# MCU.net
KiCad netlist of a schematic drawn in Altium Designer
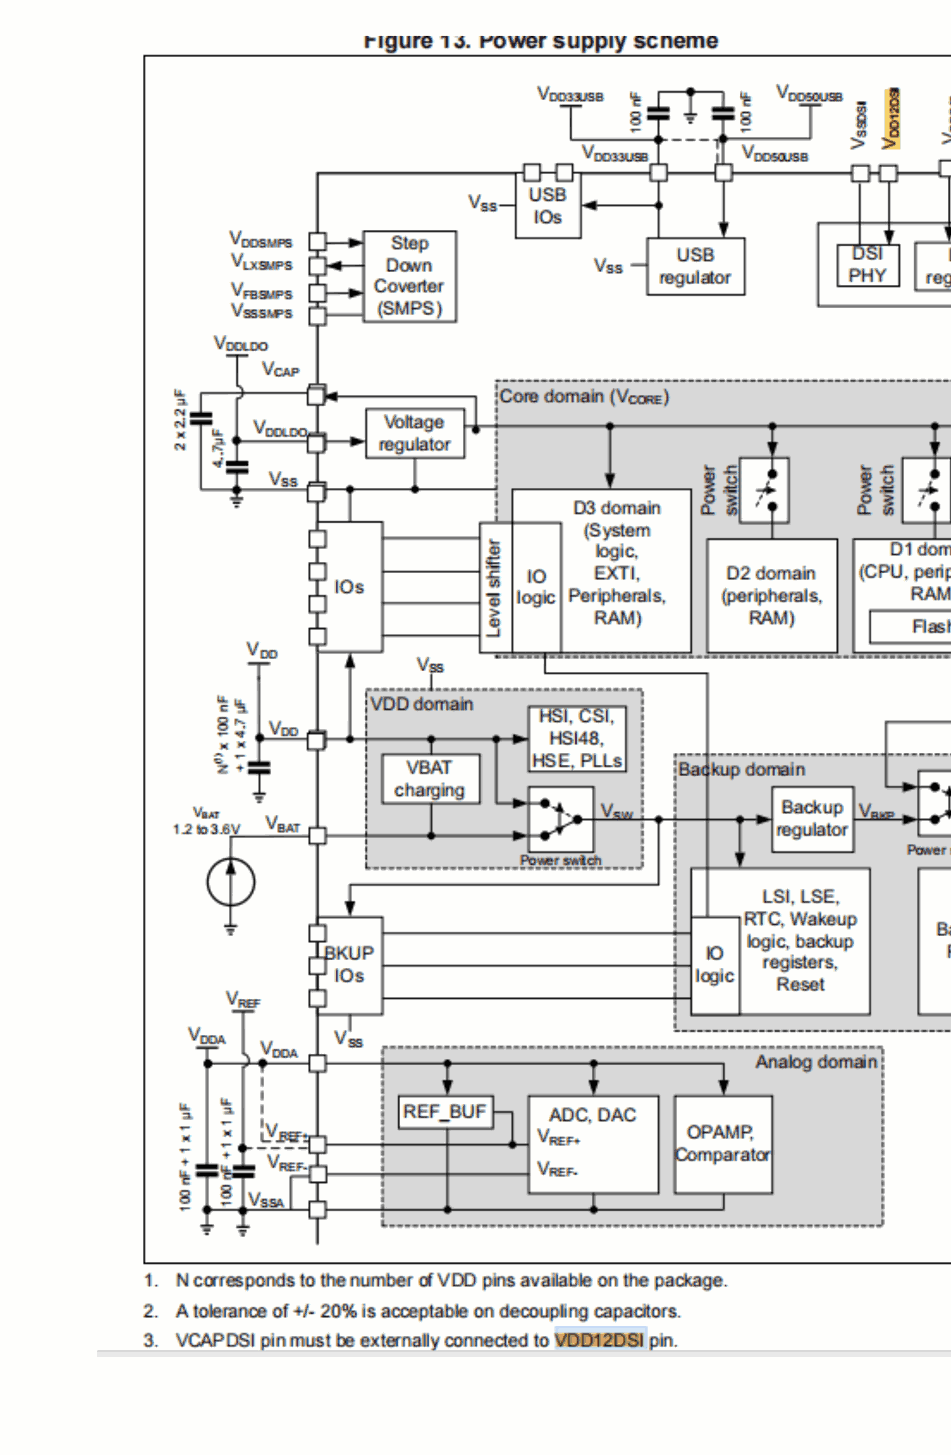
[diagram p0: MCU.SchDoc, top left]
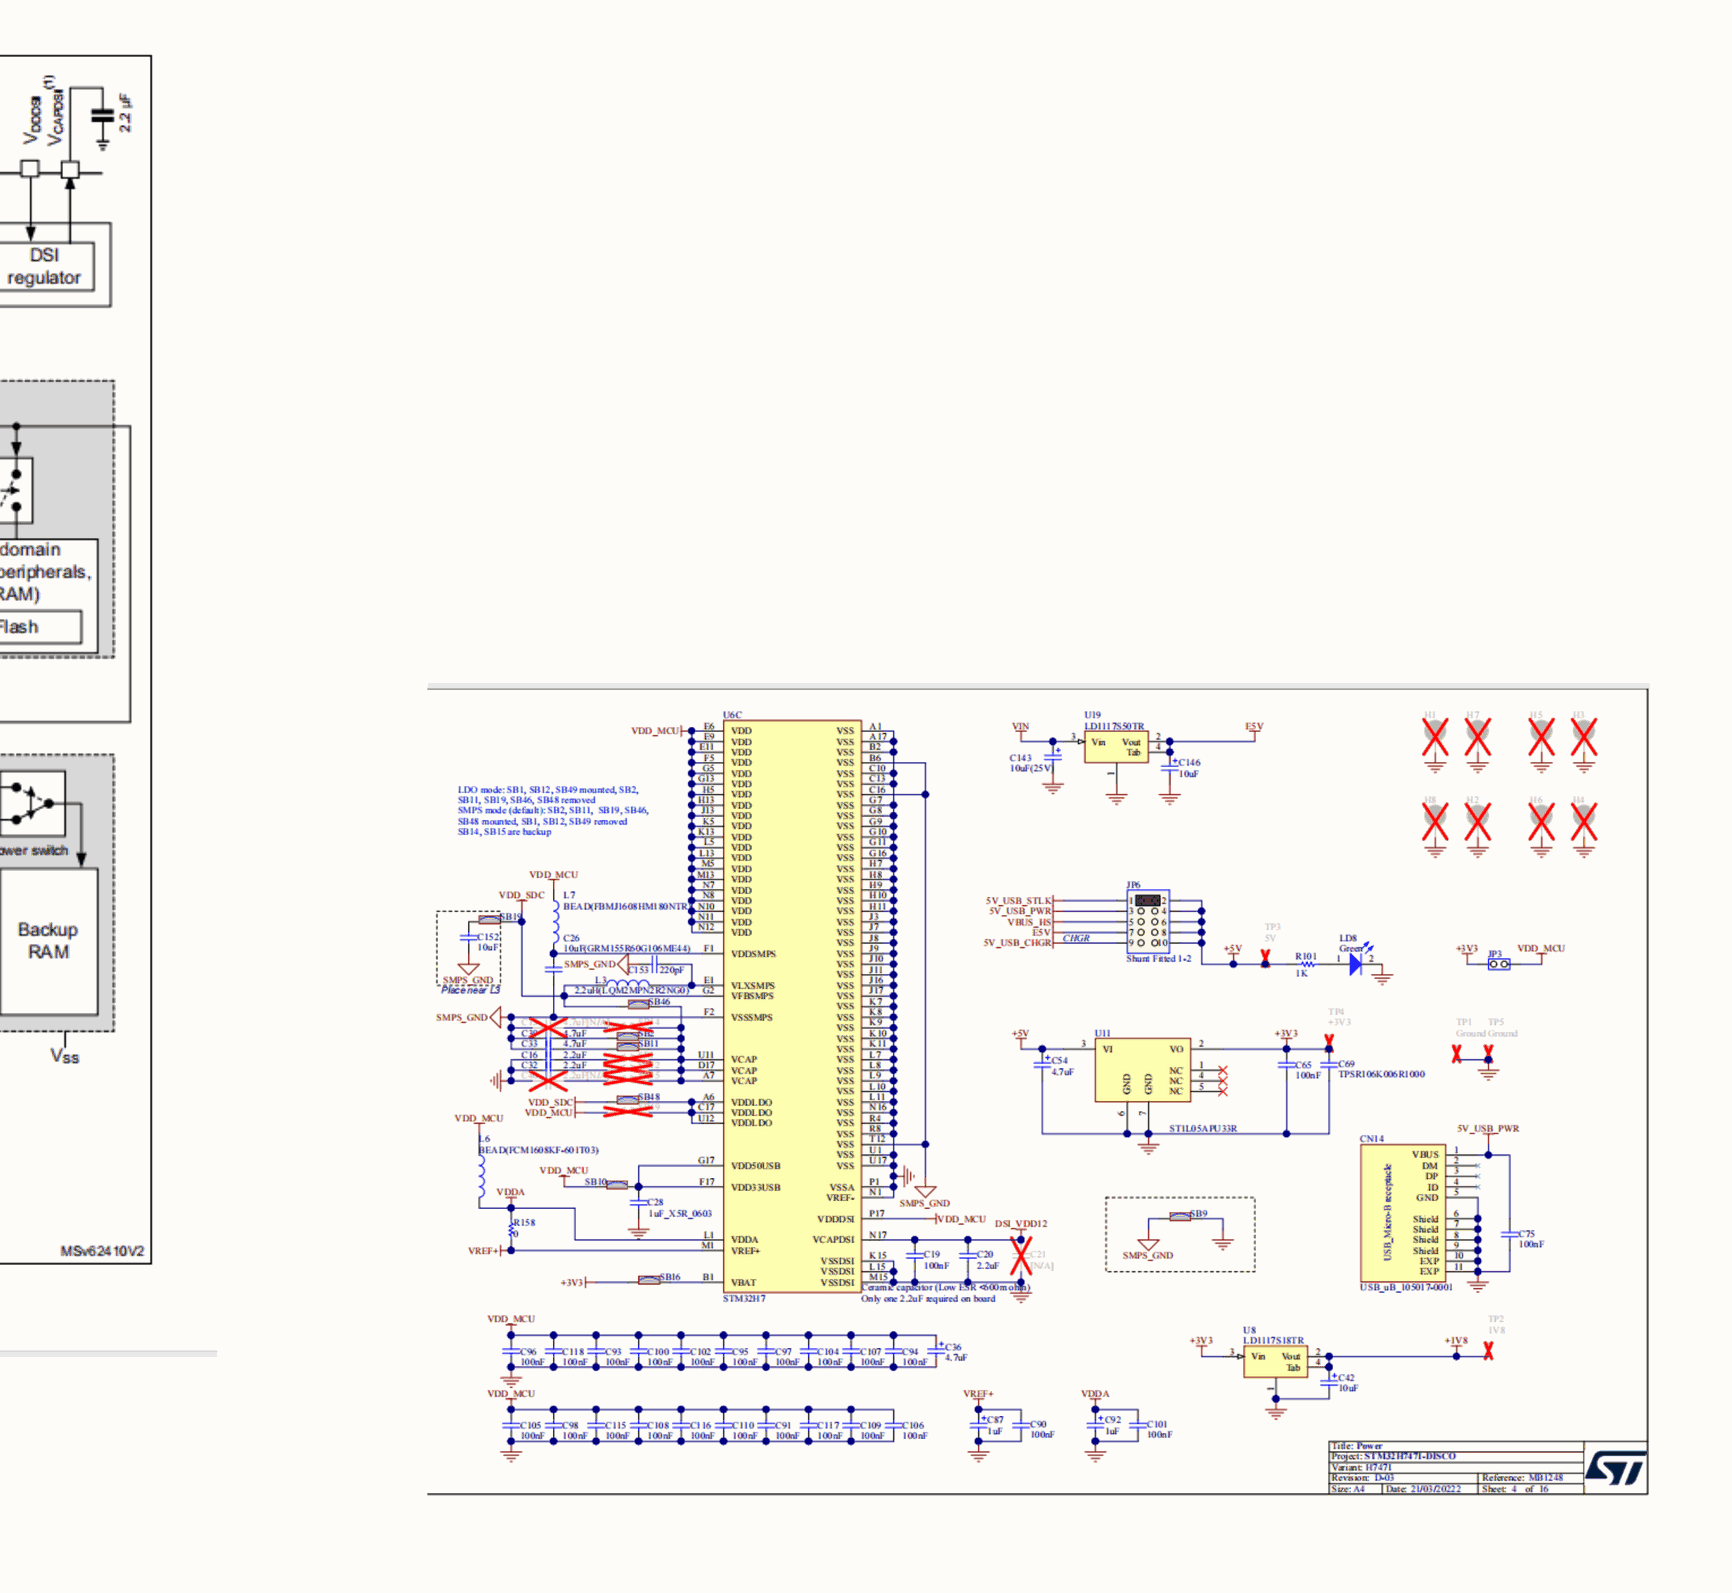
[diagram p1: MCU.SchDoc, top middle]
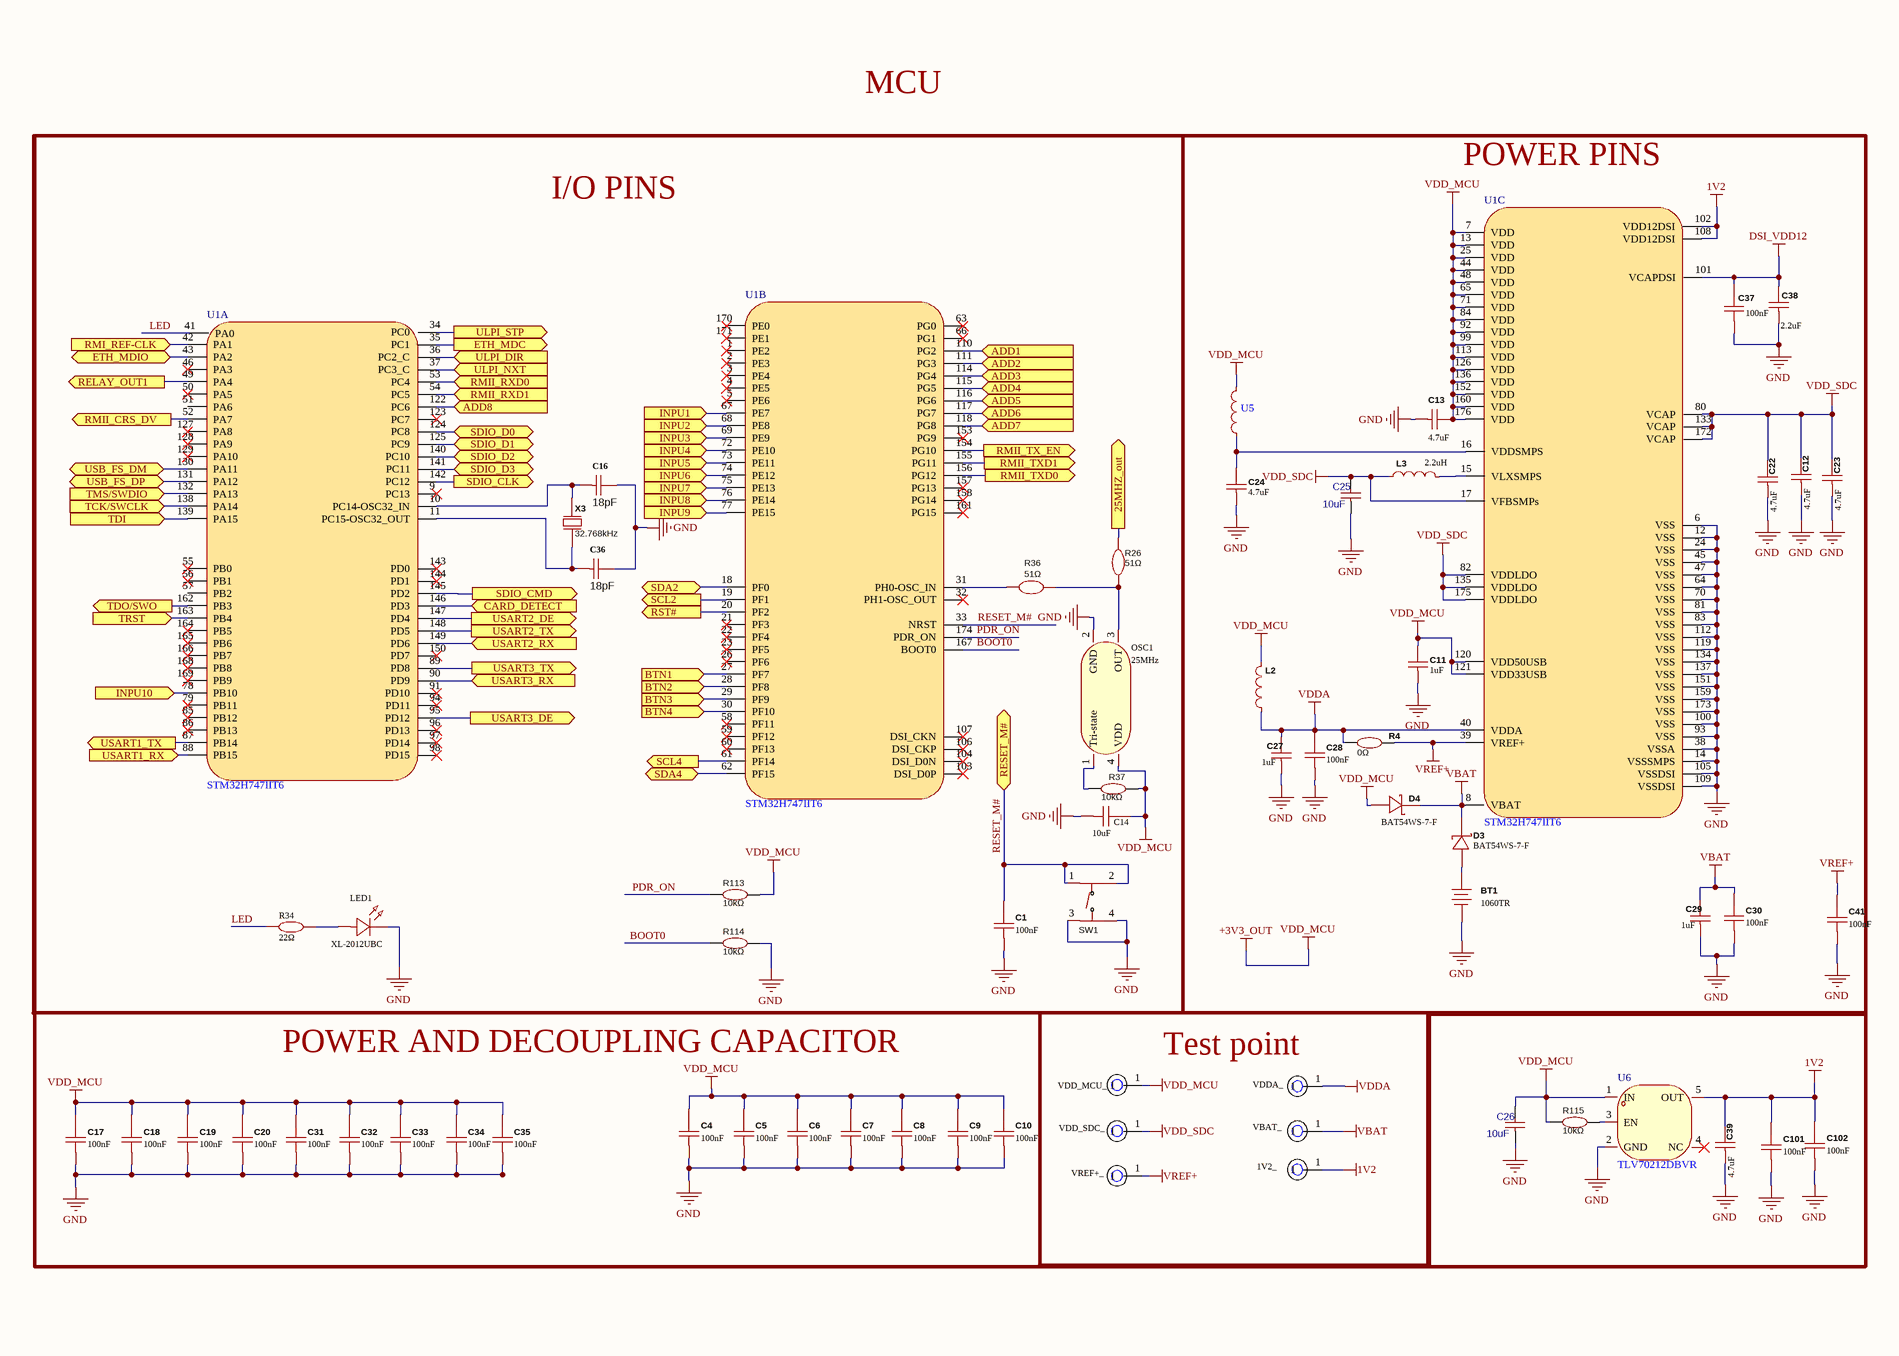
[diagram p2: MCU.SchDoc, bottom left]
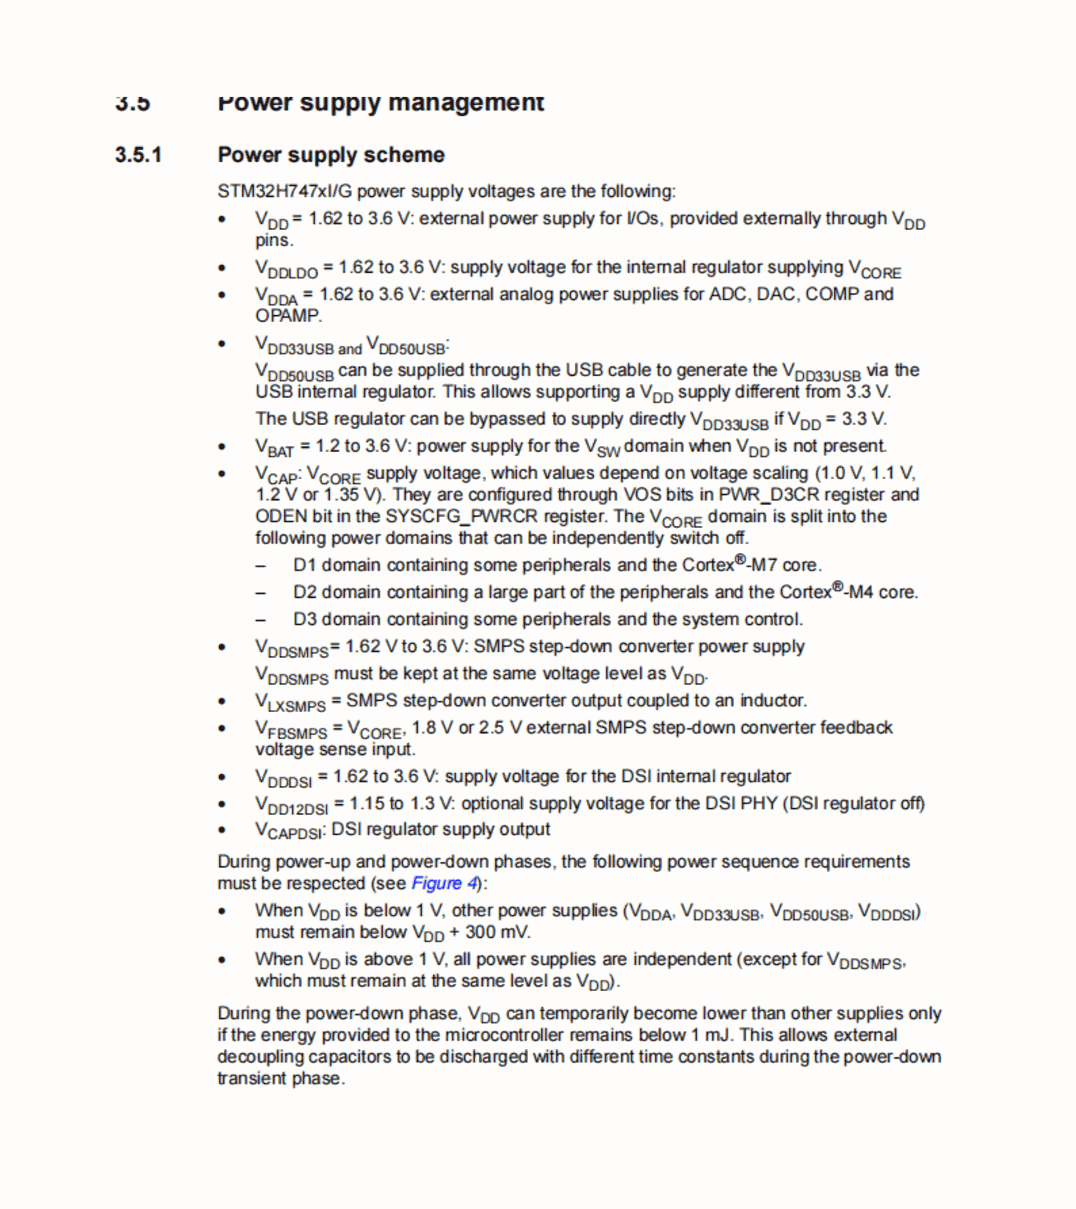
[diagram p3: MCU.SchDoc, bottom middle]
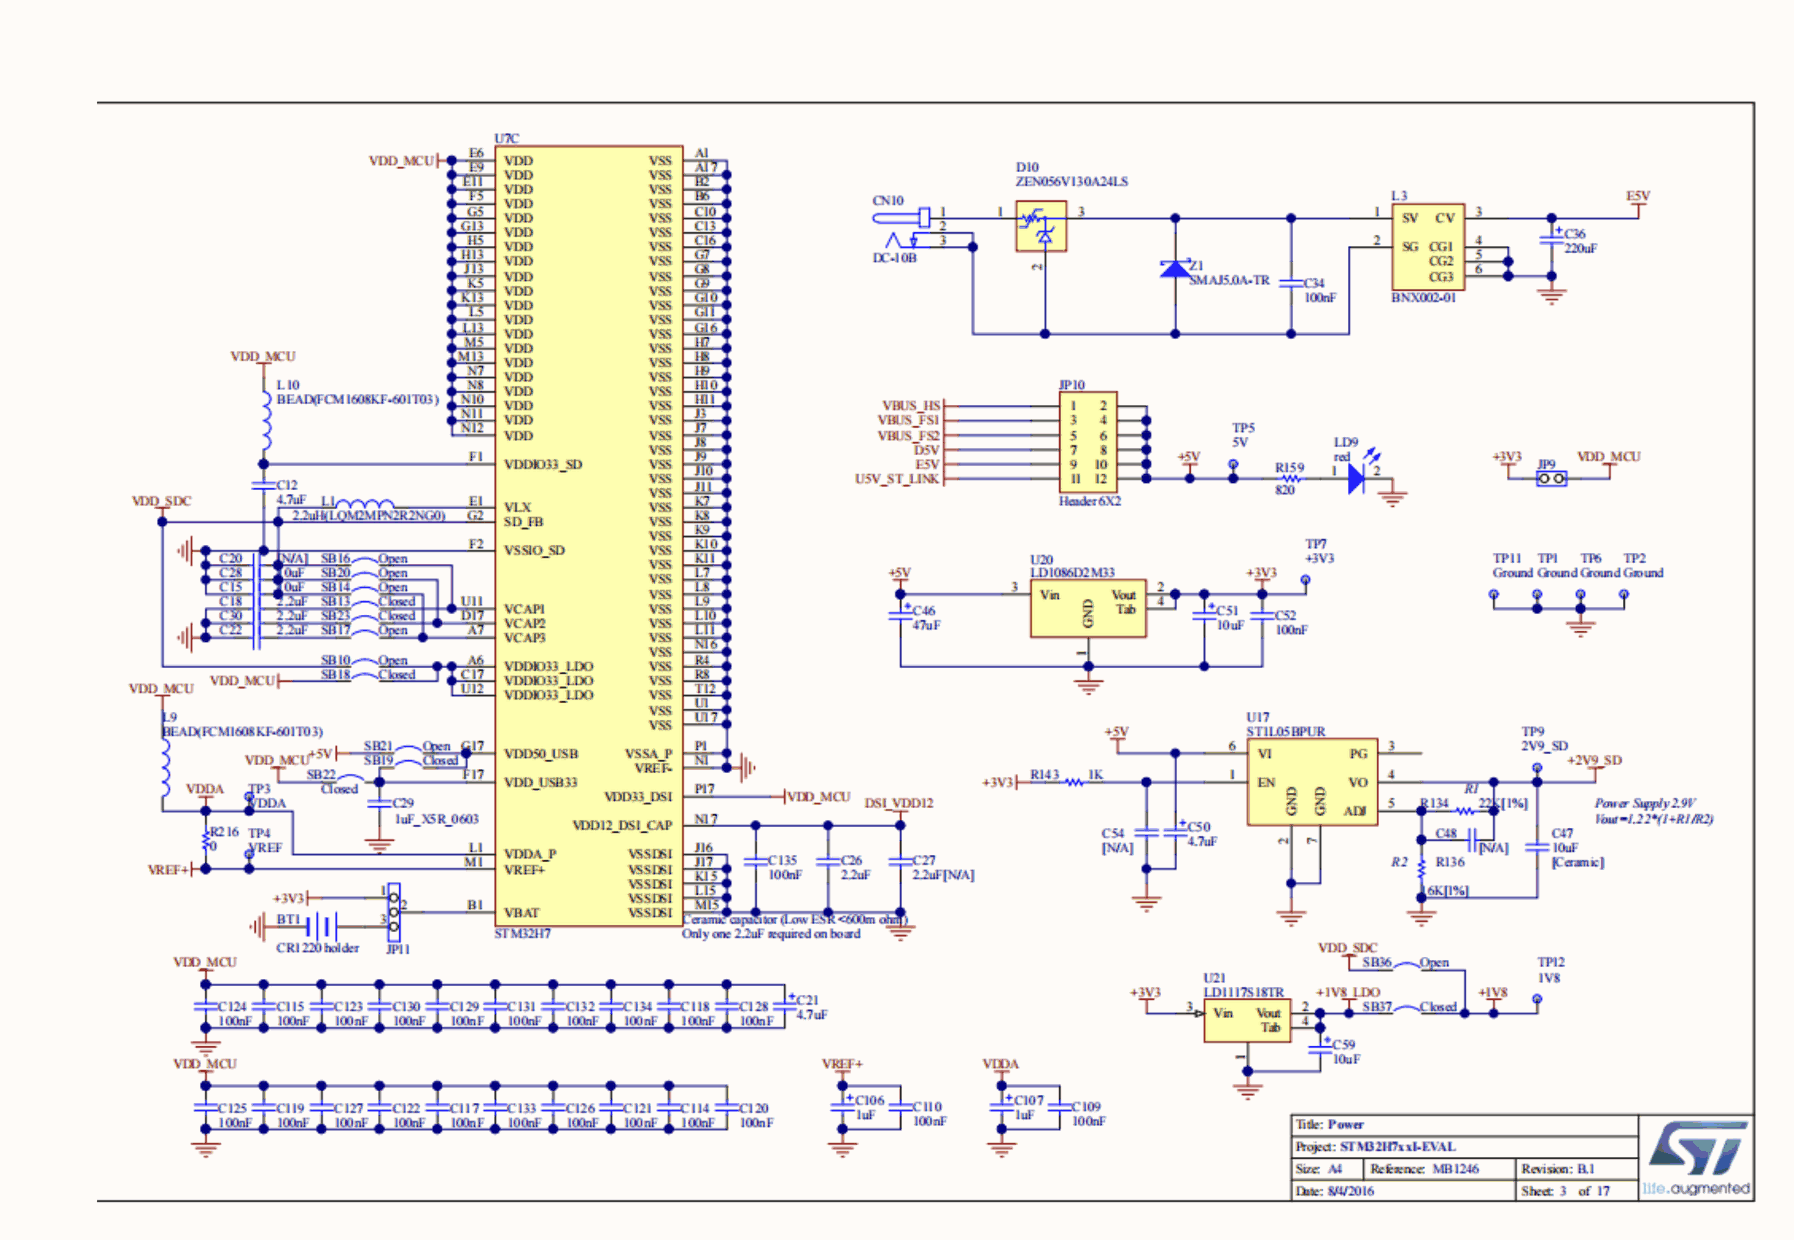
[diagram p4: MCU.SchDoc, bottom right]

(export (version "E")
  (design (tool "Eeschema 10.0.6"))
  (components
    (comp (ref "1V2_") (value "TP") (footprint "TP") (libsource (lib "Schlib1") (part "TP")))
    (comp (ref "BT1")
      (value "1060TR")
      (footprint "BAT-SMD_1060TR")
      (fields (field (name "MANUFACTURER") "Keystone"))
      (libsource (lib "altium-import") (part "root_1_1060TR_"))
    )
    (comp (ref "C1")
      (value "100nF")
      (footprint "C_0603")
      (fields
        (field (name "MANUFACTURER") "YAGEO(国巨)")
        (field (name "MANUFACTURER PART") "CC0603KRX7R9BB104")
        (field (name "TOLERANCE") "±10%")
      )
      (libsource (lib "altium-import") (part "root_3_CC0603KRX7R9BB104_"))
    )
    (comp (ref "C4")
      (value "100nF")
      (footprint "C_0603")
      (fields
        (field (name "MANUFACTURER") "YAGEO(国巨)")
        (field (name "MANUFACTURER PART") "CC0603KRX7R9BB104")
        (field (name "TOLERANCE") "±10%")
      )
      (libsource (lib "altium-import") (part "root_3_CC0603KRX7R9BB104_"))
    )
    (comp (ref "C5")
      (value "100nF")
      (footprint "C_0603")
      (fields
        (field (name "MANUFACTURER") "YAGEO(国巨)")
        (field (name "MANUFACTURER PART") "CC0603KRX7R9BB104")
        (field (name "TOLERANCE") "±10%")
      )
      (libsource (lib "altium-import") (part "root_3_CC0603KRX7R9BB104_"))
    )
    (comp (ref "C6")
      (value "100nF")
      (footprint "C_0603")
      (fields
        (field (name "MANUFACTURER") "YAGEO(国巨)")
        (field (name "MANUFACTURER PART") "CC0603KRX7R9BB104")
        (field (name "TOLERANCE") "±10%")
      )
      (libsource (lib "altium-import") (part "root_3_CC0603KRX7R9BB104_"))
    )
    (comp (ref "C7")
      (value "100nF")
      (footprint "C_0603")
      (fields
        (field (name "MANUFACTURER") "YAGEO(国巨)")
        (field (name "MANUFACTURER PART") "CC0603KRX7R9BB104")
        (field (name "TOLERANCE") "±10%")
      )
      (libsource (lib "altium-import") (part "root_3_CC0603KRX7R9BB104_"))
    )
    (comp (ref "C8")
      (value "100nF")
      (footprint "C_0603")
      (fields
        (field (name "MANUFACTURER") "YAGEO(国巨)")
        (field (name "MANUFACTURER PART") "CC0603KRX7R9BB104")
        (field (name "TOLERANCE") "±10%")
      )
      (libsource (lib "altium-import") (part "root_3_CC0603KRX7R9BB104_"))
    )
    (comp (ref "C9")
      (value "100nF")
      (footprint "C_0603")
      (fields
        (field (name "MANUFACTURER") "YAGEO(国巨)")
        (field (name "MANUFACTURER PART") "CC0603KRX7R9BB104")
        (field (name "TOLERANCE") "±10%")
      )
      (libsource (lib "altium-import") (part "root_3_CC0603KRX7R9BB104_"))
    )
    (comp (ref "C10")
      (value "100nF")
      (footprint "C_0603")
      (fields
        (field (name "MANUFACTURER") "YAGEO(国巨)")
        (field (name "MANUFACTURER PART") "CC0603KRX7R9BB104")
        (field (name "TOLERANCE") "±10%")
      )
      (libsource (lib "altium-import") (part "root_3_CC0603KRX7R9BB104_"))
    )
    (comp (ref "C11")
      (value "1uF")
      (footprint "C_0805")
      (fields
        (field (name "MANUFACTURER PART") "CL21B105KBFNNNE")
        (field (name "MANUFACTURER") "SAMSUNG(三星)")
        (field (name "TOLERANCE") "±10%")
      )
      (libsource (lib "altium-import") (part "root_1_CL21B105KBFNNNE_"))
    )
    (comp (ref "C12")
      (value "4.7uF")
      (footprint "C_0805")
      (fields
        (field (name "MANUFACTURER") "SAMSUNG(三星)")
        (field (name "MANUFACTURER PART") "CL21A475KBQNNNE")
        (field (name "TOLERANCE") "±10%")
      )
      (libsource (lib "altium-import") (part "root_1_CL21A475KBQNNNE_"))
    )
    (comp (ref "C13")
      (value "4.7uF")
      (footprint "C_0805")
      (fields
        (field (name "MANUFACTURER") "SAMSUNG(三星)")
        (field (name "MANUFACTURER PART") "CL21A475KBQNNNE")
        (field (name "TOLERANCE") "±10%")
      )
      (libsource (lib "altium-import") (part "root_0_CL21A475KBQNNNE_"))
    )
    (comp (ref "C14")
      (value "10uF")
      (footprint "C_0603")
      (fields
        (field (name "MANUFACTURER") "SAMSUNG(三星)")
        (field (name "MANUFACTURER PART") "CL10A106KP8NNNC")
        (field (name "TOLERANCE") "±10%")
      )
      (libsource (lib "altium-import") (part "root_2_CL10A106KP8NNNC_"))
    )
    (comp (ref "C16")
      (value "18pF")
      (footprint "C_0603")
      (fields
        (field (name "MANUFACTURER") "SAMSUNG(三星)")
        (field (name "MANUFACTURER PART") "CL10C180JB8NNNC")
        (field (name "TOLERANCE") "±5%")
      )
      (libsource (lib "altium-import") (part "root_0_CL10C180JB8NNNC_"))
    )
    (comp (ref "C17")
      (value "100nF")
      (footprint "C_0603")
      (fields
        (field (name "MANUFACTURER") "YAGEO(国巨)")
        (field (name "MANUFACTURER PART") "CC0603KRX7R9BB104")
        (field (name "TOLERANCE") "±10%")
      )
      (libsource (lib "altium-import") (part "root_3_CC0603KRX7R9BB104_"))
    )
    (comp (ref "C18")
      (value "100nF")
      (footprint "C_0603")
      (fields
        (field (name "MANUFACTURER") "YAGEO(国巨)")
        (field (name "MANUFACTURER PART") "CC0603KRX7R9BB104")
        (field (name "TOLERANCE") "±10%")
      )
      (libsource (lib "altium-import") (part "root_3_CC0603KRX7R9BB104_"))
    )
    (comp (ref "C19")
      (value "100nF")
      (footprint "C_0603")
      (fields
        (field (name "MANUFACTURER") "YAGEO(国巨)")
        (field (name "MANUFACTURER PART") "CC0603KRX7R9BB104")
        (field (name "TOLERANCE") "±10%")
      )
      (libsource (lib "altium-import") (part "root_3_CC0603KRX7R9BB104_"))
    )
    (comp (ref "C20")
      (value "100nF")
      (footprint "C_0603")
      (fields
        (field (name "MANUFACTURER") "YAGEO(国巨)")
        (field (name "MANUFACTURER PART") "CC0603KRX7R9BB104")
        (field (name "TOLERANCE") "±10%")
      )
      (libsource (lib "altium-import") (part "root_3_CC0603KRX7R9BB104_"))
    )
    (comp (ref "C22")
      (value "4.7uF")
      (footprint "C_0805")
      (fields
        (field (name "MANUFACTURER") "SAMSUNG(三星)")
        (field (name "MANUFACTURER PART") "CL21A475KBQNNNE")
        (field (name "TOLERANCE") "±10%")
      )
      (libsource (lib "altium-import") (part "root_1_CL21A475KBQNNNE_"))
    )
    (comp (ref "C23")
      (value "4.7uF")
      (footprint "C_0805")
      (fields
        (field (name "MANUFACTURER") "SAMSUNG(三星)")
        (field (name "MANUFACTURER PART") "CL21A475KBQNNNE")
        (field (name "TOLERANCE") "±10%")
      )
      (libsource (lib "altium-import") (part "root_1_CL21A475KBQNNNE_"))
    )
    (comp (ref "C24")
      (value "4.7uF")
      (footprint "C_0805")
      (fields
        (field (name "MANUFACTURER") "SAMSUNG(三星)")
        (field (name "MANUFACTURER PART") "CL21A475KBQNNNE")
        (field (name "TOLERANCE") "±10%")
      )
      (libsource (lib "altium-import") (part "root_1_CL21A475KBQNNNE_"))
    )
    (comp (ref "C25")
      (value "10uF")
      (footprint "C_0805")
      (fields
        (field (name "MANUFACTURER PART") "CL21A106KOQNNNE")
        (field (name "MANUFACTURER") "SAMSUNG(三星)")
      )
      (libsource (lib "altium-import") (part "root_1_10uF_"))
    )
    (comp (ref "C26")
      (value "10uF")
      (footprint "C_0805")
      (fields
        (field (name "MANUFACTURER PART") "CL21A106KOQNNNE")
        (field (name "MANUFACTURER") "SAMSUNG(三星)")
      )
      (libsource (lib "altium-import") (part "root_1_10uF_"))
    )
    (comp (ref "C27")
      (value "1uF")
      (footprint "C_0805")
      (fields
        (field (name "MANUFACTURER PART") "CL21B105KBFNNNE")
        (field (name "MANUFACTURER") "SAMSUNG(三星)")
        (field (name "TOLERANCE") "±10%")
      )
      (libsource (lib "altium-import") (part "root_1_CL21B105KBFNNNE_"))
    )
    (comp (ref "C28")
      (value "100nF")
      (footprint "C_0603")
      (fields
        (field (name "MANUFACTURER") "YAGEO(国巨)")
        (field (name "MANUFACTURER PART") "CC0603KRX7R9BB104")
        (field (name "TOLERANCE") "±10%")
      )
      (libsource (lib "altium-import") (part "root_3_CC0603KRX7R9BB104_"))
    )
    (comp (ref "C29")
      (value "1uF")
      (footprint "C_0805")
      (fields
        (field (name "MANUFACTURER PART") "CL21B105KBFNNNE")
        (field (name "MANUFACTURER") "SAMSUNG(三星)")
        (field (name "TOLERANCE") "±10%")
      )
      (libsource (lib "altium-import") (part "root_1_CL21B105KBFNNNE_"))
    )
    (comp (ref "C30")
      (value "100nF")
      (footprint "C_0603")
      (fields
        (field (name "MANUFACTURER") "YAGEO(国巨)")
        (field (name "MANUFACTURER PART") "CC0603KRX7R9BB104")
        (field (name "TOLERANCE") "±10%")
      )
      (libsource (lib "altium-import") (part "root_3_CC0603KRX7R9BB104_"))
    )
    (comp (ref "C31")
      (value "100nF")
      (footprint "C_0603")
      (fields
        (field (name "MANUFACTURER") "YAGEO(国巨)")
        (field (name "MANUFACTURER PART") "CC0603KRX7R9BB104")
        (field (name "TOLERANCE") "±10%")
      )
      (libsource (lib "altium-import") (part "root_3_CC0603KRX7R9BB104_"))
    )
    (comp (ref "C32")
      (value "100nF")
      (footprint "C_0603")
      (fields
        (field (name "MANUFACTURER") "YAGEO(国巨)")
        (field (name "MANUFACTURER PART") "CC0603KRX7R9BB104")
        (field (name "TOLERANCE") "±10%")
      )
      (libsource (lib "altium-import") (part "root_3_CC0603KRX7R9BB104_"))
    )
    (comp (ref "C33")
      (value "100nF")
      (footprint "C_0603")
      (fields
        (field (name "MANUFACTURER") "YAGEO(国巨)")
        (field (name "MANUFACTURER PART") "CC0603KRX7R9BB104")
        (field (name "TOLERANCE") "±10%")
      )
      (libsource (lib "altium-import") (part "root_3_CC0603KRX7R9BB104_"))
    )
    (comp (ref "C34")
      (value "100nF")
      (footprint "C_0603")
      (fields
        (field (name "MANUFACTURER") "YAGEO(国巨)")
        (field (name "MANUFACTURER PART") "CC0603KRX7R9BB104")
        (field (name "TOLERANCE") "±10%")
      )
      (libsource (lib "altium-import") (part "root_3_CC0603KRX7R9BB104_"))
    )
    (comp (ref "C35")
      (value "100nF")
      (footprint "C_0603")
      (fields
        (field (name "MANUFACTURER") "YAGEO(国巨)")
        (field (name "MANUFACTURER PART") "CC0603KRX7R9BB104")
        (field (name "TOLERANCE") "±10%")
      )
      (libsource (lib "altium-import") (part "root_3_CC0603KRX7R9BB104_"))
    )
    (comp (ref "C36")
      (value "18pF")
      (footprint "C_0603")
      (fields
        (field (name "MANUFACTURER") "SAMSUNG(三星)")
        (field (name "MANUFACTURER PART") "CL10C180JB8NNNC")
        (field (name "TOLERANCE") "±5%")
      )
      (libsource (lib "altium-import") (part "root_0_CL10C180JB8NNNC_"))
    )
    (comp (ref "C37")
      (value "100nF")
      (footprint "C_0603")
      (fields
        (field (name "MANUFACTURER") "YAGEO(国巨)")
        (field (name "MANUFACTURER PART") "CC0603KRX7R9BB104")
        (field (name "TOLERANCE") "±10%")
      )
      (libsource (lib "altium-import") (part "root_3_CC0603KRX7R9BB104_"))
    )
    (comp (ref "C38")
      (value "2.2uF")
      (footprint "C_0805")
      (fields
        (field (name "MANUFACTURER") "SAMSUNG(三星)")
        (field (name "MANUFACTURER PART") "CL21B225KAFNNNE")
        (field (name "TOLERANCE") "±10%")
      )
      (libsource (lib "altium-import") (part "root_1_CL21B225KAFNNNE_"))
    )
    (comp (ref "C39")
      (value "4.7uF")
      (footprint "C_0805")
      (fields
        (field (name "MANUFACTURER") "SAMSUNG(三星)")
        (field (name "MANUFACTURER PART") "CL21A475KBQNNNE")
        (field (name "TOLERANCE") "±10%")
      )
      (libsource (lib "altium-import") (part "root_1_CL21A475KBQNNNE_"))
    )
    (comp (ref "C41")
      (value "100nF")
      (footprint "C_0603")
      (fields
        (field (name "MANUFACTURER") "YAGEO(国巨)")
        (field (name "MANUFACTURER PART") "CC0603KRX7R9BB104")
        (field (name "TOLERANCE") "±10%")
      )
      (libsource (lib "altium-import") (part "root_3_CC0603KRX7R9BB104_"))
    )
    (comp (ref "C101")
      (value "100nF")
      (footprint "C_0603")
      (fields
        (field (name "MANUFACTURER") "YAGEO(国巨)")
        (field (name "MANUFACTURER PART") "CC0603KRX7R9BB104")
        (field (name "TOLERANCE") "±10%")
      )
      (libsource (lib "altium-import") (part "root_3_CC0603KRX7R9BB104_"))
    )
    (comp (ref "C102")
      (value "100nF")
      (footprint "C_0603")
      (fields
        (field (name "MANUFACTURER") "YAGEO(国巨)")
        (field (name "MANUFACTURER PART") "CC0603KRX7R9BB104")
        (field (name "TOLERANCE") "±10%")
      )
      (libsource (lib "altium-import") (part "root_3_CC0603KRX7R9BB104_"))
    )
    (comp (ref "D3")
      (value "BAT54WS-7-F")
      (footprint "SOD-323_L1.8-W1.3-LS2.5-RD")
      (fields (field (name "MANUFACTURER") "DIODES(美台)"))
      (libsource (lib "altium-import") (part "root_3_BAT54WS-7-F_"))
    )
    (comp (ref "D4")
      (value "BAT54WS-7-F")
      (footprint "SOD-323_L1.8-W1.3-LS2.5-RD")
      (fields (field (name "MANUFACTURER") "DIODES(美台)"))
      (libsource (lib "altium-import") (part "root_2_BAT54WS-7-F_"))
    )
    (comp (ref "L2")
      (value "FCM1608KF-601T03")
      (footprint "R_0603")
      (fields (field (name "MANUFACTURER") "TAI-TECH(台庆)") (field (name "TOLERANCE") "±25%"))
      (libsource (lib "altium-import") (part "root_1_FCM1608KF-601T03_"))
    )
    (comp (ref "L3")
      (value "2.2uH")
      (footprint "l0806")
      (fields
        (field (name "MANUFACTURER") "muRata(村田)")
        (field (name "MANUFACTURER PART") "LQM2MPN2R2NG0L")
        (field (name "TOLERANCE") "±30%")
      )
      (libsource (lib "altium-import") (part "root_0_LQM2MPN2R2NG0L_"))
    )
    (comp (ref "LED1")
      (value "XL-2012UBC")
      (footprint "LED0805-RD")
      (fields (field (name "MANUFACTURER") "XINGLIGHT(成兴光)"))
      (libsource (lib "altium-import") (part "root_0_mirrored_XL-2012UBC_"))
    )
    (comp (ref "OSC1")
      (value "25MHz")
      (footprint "OSC-SMD_4P-L2.5-W2.0-BL")
      (fields
        (field (name "MANUFACTURER") "YXC(扬兴晶振)")
        (field (name "MANUFACTURER PART") "OT3EL89CJI-111YLC-25M")
      )
      (libsource (lib "altium-import") (part "root_1_mirrored_OT3EL89CJI-111YLC-25M_"))
    )
    (comp (ref "R4")
      (value "0Ω")
      (footprint "R_0402")
      (fields (field (name "MANUFACTURER") "YAGEO(国巨)") (field (name "MANUFACTURER PART") "RC0402FR-070RL"))
      (libsource (lib "altium-import") (part "root_2_0Ω_"))
    )
    (comp (ref "R26")
      (value "51Ω")
      (footprint "R_0603")
      (fields
        (field (name "MANUFACTURER") "FOJAN(富捷)")
        (field (name "MANUFACTURER PART") "FRC0603J510 TS")
        (field (name "CONTRIBUTOR") "lcsc")
      )
      (libsource (lib "altium-import") (part "root_1_51Ω_"))
    )
    (comp (ref "R34")
      (value "22Ω")
      (footprint "R_0603")
      (fields
        (field (name "MANUFACTURER") "YAGEO(国巨)")
        (field (name "MANUFACTURER PART") "RC0603FR-0722RL")
        (field (name "TOLERANCE") "±1%")
      )
      (libsource (lib "altium-import") (part "root_0_mirrored_RC0603FR-0722RL_"))
    )
    (comp (ref "R36")
      (value "51Ω")
      (footprint "R_0603")
      (fields
        (field (name "MANUFACTURER") "FOJAN(富捷)")
        (field (name "MANUFACTURER PART") "FRC0603J510 TS")
        (field (name "CONTRIBUTOR") "lcsc")
      )
      (libsource (lib "altium-import") (part "root_0_51Ω_"))
    )
    (comp (ref "R37")
      (value "10kΩ")
      (footprint "R_0603")
      (fields (field (name "MANUFACTURER") "YAGEO(国巨)") (field (name "MANUFACTURER PART") "RC0603FR-0710KL"))
      (libsource (lib "altium-import") (part "root_2_10kΩ_"))
    )
    (comp (ref "R113")
      (value "10kΩ")
      (footprint "R_0603")
      (fields (field (name "MANUFACTURER") "YAGEO(国巨)") (field (name "MANUFACTURER PART") "RC0603FR-0710KL"))
      (libsource (lib "altium-import") (part "root_2_10kΩ_"))
    )
    (comp (ref "R114")
      (value "10kΩ")
      (footprint "R_0603")
      (fields (field (name "MANUFACTURER") "YAGEO(国巨)") (field (name "MANUFACTURER PART") "RC0603FR-0710KL"))
      (libsource (lib "altium-import") (part "root_2_10kΩ_"))
    )
    (comp (ref "R115")
      (value "10kΩ")
      (footprint "R_0603")
      (fields (field (name "MANUFACTURER") "YAGEO(国巨)") (field (name "MANUFACTURER PART") "RC0603FR-0710KL"))
      (libsource (lib "altium-import") (part "root_0_10kΩ_"))
    )
    (comp (ref "SW1")
      (value "TS-1187A-B-A-B")
      (footprint "SW-SMD_4P-L5.1-W5.1-P3.70-LS6.5-TL_H1.5")
      (fields (field (name "MANUFACTURER") "XKB Connection(中国星坤)"))
      (libsource (lib "EsoCore_Edge_Board_V1-0.0.0") (part "TS-1187A-B-A-B"))
    )
    (comp (ref "U1")
      (value "STM32H747IIT6")
      (footprint "LQFP-176_L24.0-W24.0-P0.50-LS26.0-BL")
      (fields (field (name "MANUFACTURER") "ST(意法半导体)"))
      (libsource (lib "EsoCore_Edge_Board_V1-0.0.0") (part "STM32H747IIT6"))
    )
    (comp (ref "U5")
      (value "ferrite_bead")
      (footprint "L_0603")
      (fields
        (field (name "MANUFACTURER") "muRata(村田)")
        (field (name "MANUFACTURER PART") "BLM18PG121SN1D")
        (field (name "TOLERANCE") "±25%")
      )
      (libsource (lib "altium-import") (part "root_1_BLM18PG121SN1D_"))
    )
    (comp (ref "U6")
      (value "TLV70212DBVR")
      (footprint "SOT-23-5_L3.0-W1.7-P0.95-LS2.8-BL")
      (fields (field (name "MANUFACTURER") "TI(德州仪器)"))
      (libsource (lib "altium-import") (part "root_0_TLV70212DBVR_"))
    )
    (comp (ref "VBAT_") (value "TP") (footprint "TP") (libsource (lib "Schlib1") (part "TP")))
    (comp (ref "VDDA_") (value "TP") (footprint "TP") (libsource (lib "Schlib1") (part "TP")))
    (comp (ref "VDD_MCU_") (value "TP") (footprint "TP") (libsource (lib "Schlib1") (part "TP")))
    (comp (ref "VDD_SDC_") (value "TP") (footprint "TP") (libsource (lib "Schlib1") (part "TP")))
    (comp (ref "VREF+_") (value "TP") (footprint "TP") (libsource (lib "Schlib1") (part "TP")))
    (comp (ref "X3")
      (value "32.768kHz")
      (footprint "OSC-SMD_2P-L3.2-W1.5")
      (fields (field (name "MANUFACTURER") "ABRACON") (field (name "MANUFACTURER PART") "ABS07-32.768KHZ-T"))
      (libsource (lib "altium-import") (part "root_3_ABS07-32.768KHZ-T_"))
    )
  )
  (nets
    (net (code "1") (name "+3V3_OUT") (class "Default")
      (node (ref "C10") (pin "1") (pinfunction "1_1") (pintype "passive"))
      (node (ref "C11") (pin "2") (pinfunction "2_2") (pintype "passive"))
      (node (ref "C13") (pin "2") (pinfunction "2_2") (pintype "passive"))
      (node (ref "C14") (pin "1") (pinfunction "1_1") (pintype "passive"))
      (node (ref "C17") (pin "1") (pinfunction "1_1") (pintype "passive"))
      (node (ref "C18") (pin "1") (pinfunction "1_1") (pintype "passive"))
      (node (ref "C19") (pin "1") (pinfunction "1_1") (pintype "passive"))
      (node (ref "C20") (pin "1") (pinfunction "1_1") (pintype "passive"))
      (node (ref "C26") (pin "2") (pinfunction "2_2") (pintype "passive"))
      (node (ref "C31") (pin "1") (pinfunction "1_1") (pintype "passive"))
      (node (ref "C32") (pin "1") (pinfunction "1_1") (pintype "passive"))
      (node (ref "C33") (pin "1") (pinfunction "1_1") (pintype "passive"))
      (node (ref "C34") (pin "1") (pinfunction "1_1") (pintype "passive"))
      (node (ref "C35") (pin "1") (pinfunction "1_1") (pintype "passive"))
      (node (ref "C4") (pin "1") (pinfunction "1_1") (pintype "passive"))
      (node (ref "C5") (pin "1") (pinfunction "1_1") (pintype "passive"))
      (node (ref "C6") (pin "1") (pinfunction "1_1") (pintype "passive"))
      (node (ref "C7") (pin "1") (pinfunction "1_1") (pintype "passive"))
      (node (ref "C8") (pin "1") (pinfunction "1_1") (pintype "passive"))
      (node (ref "C9") (pin "1") (pinfunction "1_1") (pintype "passive"))
      (node (ref "D4") (pin "2") (pinfunction "2_2") (pintype "passive"))
      (node (ref "L2") (pin "2") (pinfunction "2_2") (pintype "passive"))
      (node (ref "OSC1") (pin "4") (pinfunction "VDD_4") (pintype "passive"))
      (node (ref "R113") (pin "1") (pinfunction "1_1") (pintype "passive"))
      (node (ref "R115") (pin "1") (pinfunction "1_1") (pintype "passive"))
      (node (ref "R37") (pin "1") (pinfunction "1_1") (pintype "passive"))
      (node (ref "U1") (pin "113") (pinfunction "VDD_113") (pintype "passive"))
      (node (ref "U1") (pin "120") (pinfunction "VDD50USB_120") (pintype "passive"))
      (node (ref "U1") (pin "121") (pinfunction "VDD33USB_121") (pintype "passive"))
      (node (ref "U1") (pin "126") (pinfunction "VDD_126") (pintype "passive"))
      (node (ref "U1") (pin "13") (pinfunction "VDD_13") (pintype "passive"))
      (node (ref "U1") (pin "136") (pinfunction "VDD_136") (pintype "passive"))
      (node (ref "U1") (pin "152") (pinfunction "VDD_152") (pintype "passive"))
      (node (ref "U1") (pin "160") (pinfunction "VDD_160") (pintype "passive"))
      (node (ref "U1") (pin "176") (pinfunction "VDD_176") (pintype "passive"))
      (node (ref "U1") (pin "25") (pinfunction "VDD_25") (pintype "passive"))
      (node (ref "U1") (pin "44") (pinfunction "VDD_44") (pintype "passive"))
      (node (ref "U1") (pin "48") (pinfunction "VDD_48") (pintype "passive"))
      (node (ref "U1") (pin "65") (pinfunction "VDD_65") (pintype "passive"))
      (node (ref "U1") (pin "7") (pinfunction "VDD_7") (pintype "passive"))
      (node (ref "U1") (pin "71") (pinfunction "VDD_71") (pintype "passive"))
      (node (ref "U1") (pin "84") (pinfunction "VDD_84") (pintype "passive"))
      (node (ref "U1") (pin "92") (pinfunction "VDD_92") (pintype "passive"))
      (node (ref "U1") (pin "99") (pinfunction "VDD_99") (pintype "passive"))
      (node (ref "U5") (pin "2") (pinfunction "2_2") (pintype "passive"))
      (node (ref "U6") (pin "1") (pinfunction "IN_1") (pintype "passive"))
      (node (ref "VDD_MCU_") (pin "1") (pinfunction "1_1") (pintype "passive"))
    )
    (net (code "2") (name "/25MHZ_out") (class "Default")
      (node (ref "R26") (pin "2") (pinfunction "2_2") (pintype "passive"))
    )
    (net (code "3") (name "/ADD1") (class "Default")
      (node (ref "U1") (pin "110") (pinfunction "PG2_110") (pintype "passive"))
    )
    (net (code "4") (name "/ADD2") (class "Default")
      (node (ref "U1") (pin "111") (pinfunction "PG3_111") (pintype "passive"))
    )
    (net (code "5") (name "/ADD3") (class "Default")
      (node (ref "U1") (pin "114") (pinfunction "PG4_114") (pintype "passive"))
    )
    (net (code "6") (name "/ADD4") (class "Default")
      (node (ref "U1") (pin "115") (pinfunction "PG5_115") (pintype "passive"))
    )
    (net (code "7") (name "/ADD5") (class "Default")
      (node (ref "U1") (pin "116") (pinfunction "PG6_116") (pintype "passive"))
    )
    (net (code "8") (name "/ADD6") (class "Default")
      (node (ref "U1") (pin "117") (pinfunction "PG7_117") (pintype "passive"))
    )
    (net (code "9") (name "/ADD7") (class "Default")
      (node (ref "U1") (pin "118") (pinfunction "PG8_118") (pintype "passive"))
    )
    (net (code "10") (name "/ADD8") (class "Default")
      (node (ref "U1") (pin "122") (pinfunction "PC6_122") (pintype "passive"))
    )
    (net (code "11") (name "/BOOT0") (class "Default")
      (node (ref "R114") (pin "2") (pinfunction "2_2") (pintype "passive"))
      (node (ref "U1") (pin "167") (pinfunction "BOOT0_167") (pintype "passive"))
    )
    (net (code "12") (name "/BTN1") (class "Default")
      (node (ref "U1") (pin "27") (pinfunction "PF7_27") (pintype "passive"))
    )
    (net (code "13") (name "/BTN2") (class "Default")
      (node (ref "U1") (pin "28") (pinfunction "PF8_28") (pintype "passive"))
    )
    (net (code "14") (name "/BTN3") (class "Default")
      (node (ref "U1") (pin "29") (pinfunction "PF9_29") (pintype "passive"))
    )
    (net (code "15") (name "/BTN4") (class "Default")
      (node (ref "U1") (pin "30") (pinfunction "PF10_30") (pintype "passive"))
    )
    (net (code "16") (name "/CARD_DETECT") (class "Default")
      (node (ref "U1") (pin "146") (pinfunction "PD3_146") (pintype "passive"))
    )
    (net (code "17") (name "/ETH_MDC") (class "Default")
      (node (ref "U1") (pin "35") (pinfunction "PC1_35") (pintype "passive"))
    )
    (net (code "18") (name "/ETH_MDIO") (class "Default")
      (node (ref "U1") (pin "43") (pinfunction "PA2_43") (pintype "passive"))
    )
    (net (code "19") (name "/INPU1") (class "Default")
      (node (ref "U1") (pin "67") (pinfunction "PE7_67") (pintype "passive"))
    )
    (net (code "20") (name "/INPU2") (class "Default")
      (node (ref "U1") (pin "68") (pinfunction "PE8_68") (pintype "passive"))
    )
    (net (code "21") (name "/INPU3") (class "Default")
      (node (ref "U1") (pin "69") (pinfunction "PE9_69") (pintype "passive"))
    )
    (net (code "22") (name "/INPU4") (class "Default")
      (node (ref "U1") (pin "72") (pinfunction "PE10_72") (pintype "passive"))
    )
    (net (code "23") (name "/INPU5") (class "Default")
      (node (ref "U1") (pin "73") (pinfunction "PE11_73") (pintype "passive"))
    )
    (net (code "24") (name "/INPU6") (class "Default")
      (node (ref "U1") (pin "74") (pinfunction "PE12_74") (pintype "passive"))
    )
    (net (code "25") (name "/INPU7") (class "Default")
      (node (ref "U1") (pin "75") (pinfunction "PE13_75") (pintype "passive"))
    )
    (net (code "26") (name "/INPU8") (class "Default")
      (node (ref "U1") (pin "76") (pinfunction "PE14_76") (pintype "passive"))
    )
    (net (code "27") (name "/INPU9") (class "Default")
      (node (ref "U1") (pin "77") (pinfunction "PE15_77") (pintype "passive"))
    )
    (net (code "28") (name "/INPU10") (class "Default")
      (node (ref "U1") (pin "78") (pinfunction "PB10_78") (pintype "passive"))
    )
    (net (code "29") (name "/LED") (class "Default")
      (node (ref "R34") (pin "2") (pinfunction "2_2") (pintype "passive"))
      (node (ref "U1") (pin "41") (pinfunction "PA0_41") (pintype "passive"))
    )
    (net (code "30") (name "/PDR_ON") (class "Default")
      (node (ref "R113") (pin "2") (pinfunction "2_2") (pintype "passive"))
      (node (ref "U1") (pin "174") (pinfunction "PDR_ON_174") (pintype "passive"))
    )
    (net (code "31") (name "/RELAY_OUT1") (class "Default")
      (node (ref "U1") (pin "49") (pinfunction "PA4_49") (pintype "passive"))
    )
    (net (code "32") (name "/RESET_M#") (class "Default")
      (node (ref "C1") (pin "1") (pinfunction "1_1") (pintype "passive"))
      (node (ref "SW1") (pin "1") (pinfunction "A_1") (pintype "passive"))
      (node (ref "SW1") (pin "2") (pinfunction "B_2") (pintype "passive"))
      (node (ref "U1") (pin "33") (pinfunction "NRST_33") (pintype "passive"))
    )
    (net (code "33") (name "/RMII_CRS_DV") (class "Default")
      (node (ref "U1") (pin "52") (pinfunction "PA7_52") (pintype "passive"))
    )
    (net (code "34") (name "/RMII_RXD0") (class "Default")
      (node (ref "U1") (pin "53") (pinfunction "PC4_53") (pintype "passive"))
    )
    (net (code "35") (name "/RMII_RXD1") (class "Default")
      (node (ref "U1") (pin "54") (pinfunction "PC5_54") (pintype "passive"))
    )
    (net (code "36") (name "/RMII_TXD0") (class "Default")
      (node (ref "U1") (pin "156") (pinfunction "PG12_156") (pintype "passive"))
    )
    (net (code "37") (name "/RMII_TXD1") (class "Default")
      (node (ref "U1") (pin "155") (pinfunction "PG11_155") (pintype "passive"))
    )
    (net (code "38") (name "/RMII_TX_EN") (class "Default")
      (node (ref "U1") (pin "154") (pinfunction "PG10_154") (pintype "passive"))
    )
    (net (code "39") (name "/RMI_REF-CLK") (class "Default")
      (node (ref "U1") (pin "42") (pinfunction "PA1_42") (pintype "passive"))
    )
    (net (code "40") (name "/RST#") (class "Default")
      (node (ref "U1") (pin "20") (pinfunction "PF2_20") (pintype "passive"))
    )
    (net (code "41") (name "/SCL2") (class "Default")
      (node (ref "U1") (pin "19") (pinfunction "PF1_19") (pintype "passive"))
    )
    (net (code "42") (name "/SCL4") (class "Default")
      (node (ref "U1") (pin "61") (pinfunction "PF14_61") (pintype "passive"))
    )
    (net (code "43") (name "/SDA2") (class "Default")
      (node (ref "U1") (pin "18") (pinfunction "PF0_18") (pintype "passive"))
    )
    (net (code "44") (name "/SDA4") (class "Default")
      (node (ref "U1") (pin "62") (pinfunction "PF15_62") (pintype "passive"))
    )
    (net (code "45") (name "/SDIO_CLK") (class "Default")
      (node (ref "U1") (pin "142") (pinfunction "PC12_142") (pintype "passive"))
    )
    (net (code "46") (name "/SDIO_CMD") (class "Default")
      (node (ref "U1") (pin "145") (pinfunction "PD2_145") (pintype "passive"))
    )
    (net (code "47") (name "/SDIO_D0") (class "Default")
      (node (ref "U1") (pin "124") (pinfunction "PC8_124") (pintype "passive"))
    )
    (net (code "48") (name "/SDIO_D1") (class "Default")
      (node (ref "U1") (pin "125") (pinfunction "PC9_125") (pintype "passive"))
    )
    (net (code "49") (name "/SDIO_D2") (class "Default")
      (node (ref "U1") (pin "140") (pinfunction "PC10_140") (pintype "passive"))
    )
    (net (code "50") (name "/SDIO_D3") (class "Default")
      (node (ref "U1") (pin "141") (pinfunction "PC11_141") (pintype "passive"))
    )
    (net (code "51") (name "/TCK{slash}SWCLK") (class "Default")
      (node (ref "U1") (pin "138") (pinfunction "PA14_138") (pintype "passive"))
    )
    (net (code "52") (name "/TDI") (class "Default")
      (node (ref "U1") (pin "139") (pinfunction "PA15_139") (pintype "passive"))
    )
    (net (code "53") (name "/TDO{slash}SWO") (class "Default")
      (node (ref "U1") (pin "162") (pinfunction "PB3_162") (pintype "passive"))
    )
    (net (code "54") (name "/TMS{slash}SWDIO") (class "Default")
      (node (ref "U1") (pin "132") (pinfunction "PA13_132") (pintype "passive"))
    )
    (net (code "55") (name "/TRST") (class "Default")
      (node (ref "U1") (pin "163") (pinfunction "PB4_163") (pintype "passive"))
    )
    (net (code "56") (name "/ULPI_DIR") (class "Default")
      (node (ref "U1") (pin "36") (pinfunction "PC2_C_36") (pintype "passive"))
    )
    (net (code "57") (name "/ULPI_NXT") (class "Default")
      (node (ref "U1") (pin "37") (pinfunction "PC3_C_37") (pintype "passive"))
    )
    (net (code "58") (name "/ULPI_STP") (class "Default")
      (node (ref "U1") (pin "34") (pinfunction "PC0_34") (pintype "passive"))
    )
    (net (code "59") (name "/USART1_RX") (class "Default")
      (node (ref "U1") (pin "88") (pinfunction "PB15_88") (pintype "passive"))
    )
    (net (code "60") (name "/USART1_TX") (class "Default")
      (node (ref "U1") (pin "87") (pinfunction "PB14_87") (pintype "passive"))
    )
    (net (code "61") (name "/USART2_DE") (class "Default")
      (node (ref "U1") (pin "147") (pinfunction "PD4_147") (pintype "passive"))
    )
    (net (code "62") (name "/USART2_RX") (class "Default")
      (node (ref "U1") (pin "149") (pinfunction "PD6_149") (pintype "passive"))
    )
    (net (code "63") (name "/USART2_TX") (class "Default")
      (node (ref "U1") (pin "148") (pinfunction "PD5_148") (pintype "passive"))
    )
    (net (code "64") (name "/USART3_DE") (class "Default")
      (node (ref "U1") (pin "95") (pinfunction "PD12_95") (pintype "passive"))
    )
    (net (code "65") (name "/USART3_RX") (class "Default")
      (node (ref "U1") (pin "90") (pinfunction "PD9_90") (pintype "passive"))
    )
    (net (code "66") (name "/USART3_TX") (class "Default")
      (node (ref "U1") (pin "89") (pinfunction "PD8_89") (pintype "passive"))
    )
    (net (code "67") (name "/USB_FS_DM") (class "Default")
      (node (ref "U1") (pin "130") (pinfunction "PA11_130") (pintype "passive"))
    )
    (net (code "68") (name "/USB_FS_DP") (class "Default")
      (node (ref "U1") (pin "131") (pinfunction "PA12_131") (pintype "passive"))
    )
    (net (code "69") (name "1V2") (class "Default")
      (node (ref "1V2_") (pin "1") (pinfunction "1_1") (pintype "passive"))
      (node (ref "C101") (pin "1") (pinfunction "1_1") (pintype "passive"))
      (node (ref "C102") (pin "1") (pinfunction "1_1") (pintype "passive"))
      (node (ref "C39") (pin "2") (pinfunction "2_2") (pintype "passive"))
      (node (ref "U1") (pin "102") (pinfunction "VDD12DSI_102") (pintype "passive"))
      (node (ref "U1") (pin "108") (pinfunction "VDD12DSI_108") (pintype "passive"))
      (node (ref "U6") (pin "5") (pinfunction "OUT_5") (pintype "passive"))
    )
    (net (code "70") (name "DSI_VDD12") (class "Default")
      (node (ref "C37") (pin "1") (pinfunction "1_1") (pintype "passive"))
      (node (ref "C38") (pin "2") (pinfunction "2_2") (pintype "passive"))
      (node (ref "U1") (pin "101") (pinfunction "VCAPDSI_101") (pintype "passive"))
    )
    (net (code "71") (name "GND") (class "Default")
      (node (ref "BT1") (pin "2") (pinfunction "-_2") (pintype "passive"))
      (node (ref "C1") (pin "2") (pinfunction "2_2") (pintype "passive"))
      (node (ref "C10") (pin "2") (pinfunction "2_2") (pintype "passive"))
      (node (ref "C101") (pin "2") (pinfunction "2_2") (pintype "passive"))
      (node (ref "C102") (pin "2") (pinfunction "2_2") (pintype "passive"))
      (node (ref "C11") (pin "1") (pinfunction "1_1") (pintype "passive"))
      (node (ref "C12") (pin "1") (pinfunction "1_1") (pintype "passive"))
      (node (ref "C13") (pin "1") (pinfunction "1_1") (pintype "passive"))
      (node (ref "C14") (pin "2") (pinfunction "2_2") (pintype "passive"))
      (node (ref "C16") (pin "2") (pinfunction "2_2") (pintype "passive"))
      (node (ref "C17") (pin "2") (pinfunction "2_2") (pintype "passive"))
      (node (ref "C18") (pin "2") (pinfunction "2_2") (pintype "passive"))
      (node (ref "C19") (pin "2") (pinfunction "2_2") (pintype "passive"))
      (node (ref "C20") (pin "2") (pinfunction "2_2") (pintype "passive"))
      (node (ref "C22") (pin "1") (pinfunction "1_1") (pintype "passive"))
      (node (ref "C23") (pin "1") (pinfunction "1_1") (pintype "passive"))
      (node (ref "C24") (pin "1") (pinfunction "1_1") (pintype "passive"))
      (node (ref "C25") (pin "1") (pinfunction "1_1") (pintype "passive"))
      (node (ref "C26") (pin "1") (pinfunction "1_1") (pintype "passive"))
      (node (ref "C27") (pin "1") (pinfunction "1_1") (pintype "passive"))
      (node (ref "C28") (pin "2") (pinfunction "2_2") (pintype "passive"))
      (node (ref "C29") (pin "1") (pinfunction "1_1") (pintype "passive"))
      (node (ref "C30") (pin "2") (pinfunction "2_2") (pintype "passive"))
      (node (ref "C31") (pin "2") (pinfunction "2_2") (pintype "passive"))
      (node (ref "C32") (pin "2") (pinfunction "2_2") (pintype "passive"))
      (node (ref "C33") (pin "2") (pinfunction "2_2") (pintype "passive"))
      (node (ref "C34") (pin "2") (pinfunction "2_2") (pintype "passive"))
      (node (ref "C35") (pin "2") (pinfunction "2_2") (pintype "passive"))
      (node (ref "C36") (pin "2") (pinfunction "2_2") (pintype "passive"))
      (node (ref "C37") (pin "2") (pinfunction "2_2") (pintype "passive"))
      (node (ref "C38") (pin "1") (pinfunction "1_1") (pintype "passive"))
      (node (ref "C39") (pin "1") (pinfunction "1_1") (pintype "passive"))
      (node (ref "C4") (pin "2") (pinfunction "2_2") (pintype "passive"))
      (node (ref "C41") (pin "2") (pinfunction "2_2") (pintype "passive"))
      (node (ref "C5") (pin "2") (pinfunction "2_2") (pintype "passive"))
      (node (ref "C6") (pin "2") (pinfunction "2_2") (pintype "passive"))
      (node (ref "C7") (pin "2") (pinfunction "2_2") (pintype "passive"))
      (node (ref "C8") (pin "2") (pinfunction "2_2") (pintype "passive"))
      (node (ref "C9") (pin "2") (pinfunction "2_2") (pintype "passive"))
      (node (ref "LED1") (pin "1") (pinfunction "K_1") (pintype "passive"))
      (node (ref "OSC1") (pin "2") (pinfunction "GND_2") (pintype "passive"))
      (node (ref "R114") (pin "1") (pinfunction "1_1") (pintype "passive"))
      (node (ref "SW1") (pin "3") (pinfunction "C_3") (pintype "passive"))
      (node (ref "SW1") (pin "4") (pinfunction "D_4") (pintype "passive"))
      (node (ref "U1") (pin "100") (pinfunction "VSS_100") (pintype "passive"))
      (node (ref "U1") (pin "105") (pinfunction "VSSDSI_105") (pintype "passive"))
      (node (ref "U1") (pin "109") (pinfunction "VSSDSI_109") (pintype "passive"))
      (node (ref "U1") (pin "112") (pinfunction "VSS_112") (pintype "passive"))
      (node (ref "U1") (pin "119") (pinfunction "VSS_119") (pintype "passive"))
      (node (ref "U1") (pin "12") (pinfunction "VSS_12") (pintype "passive"))
      (node (ref "U1") (pin "134") (pinfunction "VSS_134") (pintype "passive"))
      (node (ref "U1") (pin "137") (pinfunction "VSS_137") (pintype "passive"))
      (node (ref "U1") (pin "14") (pinfunction "VSSSMPS_14") (pintype "passive"))
      (node (ref "U1") (pin "151") (pinfunction "VSS_151") (pintype "passive"))
      (node (ref "U1") (pin "159") (pinfunction "VSS_159") (pintype "passive"))
      (node (ref "U1") (pin "173") (pinfunction "VSS_173") (pintype "passive"))
      (node (ref "U1") (pin "24") (pinfunction "VSS_24") (pintype "passive"))
      (node (ref "U1") (pin "38") (pinfunction "VSSA_38") (pintype "passive"))
      (node (ref "U1") (pin "45") (pinfunction "VSS_45") (pintype "passive"))
      (node (ref "U1") (pin "47") (pinfunction "VSS_47") (pintype "passive"))
      (node (ref "U1") (pin "6") (pinfunction "VSS_6") (pintype "passive"))
      (node (ref "U1") (pin "64") (pinfunction "VSS_64") (pintype "passive"))
      (node (ref "U1") (pin "70") (pinfunction "VSS_70") (pintype "passive"))
      (node (ref "U1") (pin "81") (pinfunction "VSS_81") (pintype "passive"))
      (node (ref "U1") (pin "83") (pinfunction "VSS_83") (pintype "passive"))
      (node (ref "U1") (pin "93") (pinfunction "VSS_93") (pintype "passive"))
      (node (ref "U6") (pin "2") (pinfunction "GND_2") (pintype "passive"))
    )
    (net (code "72") (name "Net-(BT1-+)") (class "Default")
      (node (ref "BT1") (pin "1") (pinfunction "+_1") (pintype "passive"))
      (node (ref "D3") (pin "2") (pinfunction "2_2") (pintype "passive"))
    )
    (net (code "73") (name "Net-(LED1-A)") (class "Default")
      (node (ref "LED1") (pin "2") (pinfunction "A_2") (pintype "passive"))
      (node (ref "R34") (pin "1") (pinfunction "1_1") (pintype "passive"))
    )
    (net (code "74") (name "Net-(OSC1-OUT)") (class "Default")
      (node (ref "OSC1") (pin "3") (pinfunction "OUT_3") (pintype "passive"))
      (node (ref "R26") (pin "1") (pinfunction "1_1") (pintype "passive"))
      (node (ref "R36") (pin "2") (pinfunction "2_2") (pintype "passive"))
    )
    (net (code "75") (name "Net-(OSC1-Tri-state)") (class "Default")
      (node (ref "OSC1") (pin "1") (pinfunction "Tri-state_1") (pintype "passive"))
      (node (ref "R37") (pin "2") (pinfunction "2_2") (pintype "passive"))
    )
    (net (code "76") (name "Net-(U1A-PC14-OSC32_IN)") (class "Default")
      (node (ref "C16") (pin "1") (pinfunction "1_1") (pintype "passive"))
      (node (ref "U1") (pin "10") (pinfunction "PC14-OSC32_IN_10") (pintype "passive"))
      (node (ref "X3") (pin "1") (pinfunction "OSC1_1") (pintype "passive"))
    )
    (net (code "77") (name "Net-(U1A-PC15-OSC32_OUT)") (class "Default")
      (node (ref "C36") (pin "1") (pinfunction "1_1") (pintype "passive"))
      (node (ref "U1") (pin "11") (pinfunction "PC15-OSC32_OUT_11") (pintype "passive"))
      (node (ref "X3") (pin "2") (pinfunction "OSC2_2") (pintype "passive"))
    )
    (net (code "78") (name "Net-(U1B-PH0-OSC_IN)") (class "Default")
      (node (ref "R36") (pin "1") (pinfunction "1_1") (pintype "passive"))
      (node (ref "U1") (pin "31") (pinfunction "PH0-OSC_IN_31") (pintype "passive"))
    )
    (net (code "79") (name "Net-(U1C-VDDSMPS)") (class "Default")
      (node (ref "C24") (pin "2") (pinfunction "2_2") (pintype "passive"))
      (node (ref "U1") (pin "16") (pinfunction "VDDSMPS_16") (pintype "passive"))
      (node (ref "U5") (pin "1") (pinfunction "1_1") (pintype "passive"))
    )
    (net (code "80") (name "Net-(U1C-VLXSMPS)") (class "Default")
      (node (ref "L3") (pin "2") (pinfunction "2_2") (pintype "passive"))
      (node (ref "U1") (pin "15") (pinfunction "VLXSMPS_15") (pintype "passive"))
    )
    (net (code "81") (name "Net-(U6-EN)") (class "Default")
      (node (ref "R115") (pin "2") (pinfunction "2_2") (pintype "passive"))
      (node (ref "U6") (pin "3") (pinfunction "EN_3") (pintype "passive"))
    )
    (net (code "82") (name "VBAT") (class "Default")
      (node (ref "C29") (pin "2") (pinfunction "2_2") (pintype "passive"))
      (node (ref "C30") (pin "1") (pinfunction "1_1") (pintype "passive"))
      (node (ref "D3") (pin "1") (pinfunction "1_1") (pintype "passive"))
      (node (ref "D4") (pin "1") (pinfunction "1_1") (pintype "passive"))
      (node (ref "U1") (pin "8") (pinfunction "VBAT_8") (pintype "passive"))
      (node (ref "VBAT_") (pin "1") (pinfunction "1_1") (pintype "passive"))
    )
    (net (code "83") (name "VDDA") (class "Default")
      (node (ref "C27") (pin "2") (pinfunction "2_2") (pintype "passive"))
      (node (ref "C28") (pin "1") (pinfunction "1_1") (pintype "passive"))
      (node (ref "L2") (pin "1") (pinfunction "1_1") (pintype "passive"))
      (node (ref "R4") (pin "2") (pinfunction "2_2") (pintype "passive"))
      (node (ref "U1") (pin "40") (pinfunction "VDDA_40") (pintype "passive"))
      (node (ref "VDDA_") (pin "1") (pinfunction "1_1") (pintype "passive"))
    )
    (net (code "84") (name "VDD_SDC") (class "Default")
      (node (ref "C12") (pin "2") (pinfunction "2_2") (pintype "passive"))
      (node (ref "C22") (pin "2") (pinfunction "2_2") (pintype "passive"))
      (node (ref "C23") (pin "2") (pinfunction "2_2") (pintype "passive"))
      (node (ref "C25") (pin "2") (pinfunction "2_2") (pintype "passive"))
      (node (ref "L3") (pin "1") (pinfunction "1_1") (pintype "passive"))
      (node (ref "U1") (pin "133") (pinfunction "VCAP_133") (pintype "passive"))
      (node (ref "U1") (pin "135") (pinfunction "VDDLDO_135") (pintype "passive"))
      (node (ref "U1") (pin "17") (pinfunction "VFBSMPs_17") (pintype "passive"))
      (node (ref "U1") (pin "172") (pinfunction "VCAP_172") (pintype "passive"))
      (node (ref "U1") (pin "175") (pinfunction "VDDLDO_175") (pintype "passive"))
      (node (ref "U1") (pin "80") (pinfunction "VCAP_80") (pintype "passive"))
      (node (ref "U1") (pin "82") (pinfunction "VDDLDO_82") (pintype "passive"))
      (node (ref "VDD_SDC_") (pin "1") (pinfunction "1_1") (pintype "passive"))
    )
    (net (code "85") (name "VREF+") (class "Default")
      (node (ref "C41") (pin "1") (pinfunction "1_1") (pintype "passive"))
      (node (ref "R4") (pin "1") (pinfunction "1_1") (pintype "passive"))
      (node (ref "U1") (pin "39") (pinfunction "VREF+_39") (pintype "passive"))
      (node (ref "VREF+_") (pin "1") (pinfunction "1_1") (pintype "passive"))
    )
    (net (code "86") (name "unconnected-(U1A-PA3-Pad46)") (class "Default")
      (node (ref "U1") (pin "46") (pinfunction "PA3_46") (pintype "passive+no_connect"))
    )
    (net (code "87") (name "unconnected-(U1A-PA5-Pad50)") (class "Default")
      (node (ref "U1") (pin "50") (pinfunction "PA5_50") (pintype "passive+no_connect"))
    )
    (net (code "88") (name "unconnected-(U1A-PA6-Pad51)") (class "Default")
      (node (ref "U1") (pin "51") (pinfunction "PA6_51") (pintype "passive"))
    )
    (net (code "89") (name "unconnected-(U1A-PA8-Pad127)") (class "Default")
      (node (ref "U1") (pin "127") (pinfunction "PA8_127") (pintype "passive+no_connect"))
    )
    (net (code "90") (name "unconnected-(U1A-PA9-Pad128)") (class "Default")
      (node (ref "U1") (pin "128") (pinfunction "PA9_128") (pintype "passive+no_connect"))
    )
    (net (code "91") (name "unconnected-(U1A-PA10-Pad129)") (class "Default")
      (node (ref "U1") (pin "129") (pinfunction "PA10_129") (pintype "passive+no_connect"))
    )
    (net (code "92") (name "unconnected-(U1A-PB0-Pad55)") (class "Default")
      (node (ref "U1") (pin "55") (pinfunction "PB0_55") (pintype "passive+no_connect"))
    )
    (net (code "93") (name "unconnected-(U1A-PB1-Pad56)") (class "Default")
      (node (ref "U1") (pin "56") (pinfunction "PB1_56") (pintype "passive+no_connect"))
    )
    (net (code "94") (name "unconnected-(U1A-PB2-Pad57)") (class "Default")
      (node (ref "U1") (pin "57") (pinfunction "PB2_57") (pintype "passive"))
    )
    (net (code "95") (name "unconnected-(U1A-PB5-Pad164)") (class "Default")
      (node (ref "U1") (pin "164") (pinfunction "PB5_164") (pintype "passive+no_connect"))
    )
    (net (code "96") (name "unconnected-(U1A-PB6-Pad165)") (class "Default")
      (node (ref "U1") (pin "165") (pinfunction "PB6_165") (pintype "passive+no_connect"))
    )
    (net (code "97") (name "unconnected-(U1A-PB7-Pad166)") (class "Default")
      (node (ref "U1") (pin "166") (pinfunction "PB7_166") (pintype "passive+no_connect"))
    )
    (net (code "98") (name "unconnected-(U1A-PB8-Pad168)") (class "Default")
      (node (ref "U1") (pin "168") (pinfunction "PB8_168") (pintype "passive+no_connect"))
    )
    (net (code "99") (name "unconnected-(U1A-PB9-Pad169)") (class "Default")
      (node (ref "U1") (pin "169") (pinfunction "PB9_169") (pintype "passive+no_connect"))
    )
    (net (code "100") (name "unconnected-(U1A-PB11-Pad79)") (class "Default")
      (node (ref "U1") (pin "79") (pinfunction "PB11_79") (pintype "passive+no_connect"))
    )
    (net (code "101") (name "unconnected-(U1A-PB12-Pad85)") (class "Default")
      (node (ref "U1") (pin "85") (pinfunction "PB12_85") (pintype "passive+no_connect"))
    )
    (net (code "102") (name "unconnected-(U1A-PB13-Pad86)") (class "Default")
      (node (ref "U1") (pin "86") (pinfunction "PB13_86") (pintype "passive+no_connect"))
    )
    (net (code "103") (name "unconnected-(U1A-PC7-Pad123)") (class "Default")
      (node (ref "U1") (pin "123") (pinfunction "PC7_123") (pintype "passive+no_connect"))
    )
    (net (code "104") (name "unconnected-(U1A-PC13-Pad9)") (class "Default")
      (node (ref "U1") (pin "9") (pinfunction "PC13_9") (pintype "passive+no_connect"))
    )
    (net (code "105") (name "unconnected-(U1A-PD0-Pad143)") (class "Default")
      (node (ref "U1") (pin "143") (pinfunction "PD0_143") (pintype "passive+no_connect"))
    )
    (net (code "106") (name "unconnected-(U1A-PD1-Pad144)") (class "Default")
      (node (ref "U1") (pin "144") (pinfunction "PD1_144") (pintype "passive+no_connect"))
    )
    (net (code "107") (name "unconnected-(U1A-PD7-Pad150)") (class "Default")
      (node (ref "U1") (pin "150") (pinfunction "PD7_150") (pintype "passive+no_connect"))
    )
    (net (code "108") (name "unconnected-(U1A-PD10-Pad91)") (class "Default")
      (node (ref "U1") (pin "91") (pinfunction "PD10_91") (pintype "passive+no_connect"))
    )
    (net (code "109") (name "unconnected-(U1A-PD11-Pad94)") (class "Default")
      (node (ref "U1") (pin "94") (pinfunction "PD11_94") (pintype "passive+no_connect"))
    )
    (net (code "110") (name "unconnected-(U1A-PD13-Pad96)") (class "Default")
      (node (ref "U1") (pin "96") (pinfunction "PD13_96") (pintype "passive+no_connect"))
    )
    (net (code "111") (name "unconnected-(U1A-PD14-Pad97)") (class "Default")
      (node (ref "U1") (pin "97") (pinfunction "PD14_97") (pintype "passive+no_connect"))
    )
    (net (code "112") (name "unconnected-(U1A-PD15-Pad98)") (class "Default")
      (node (ref "U1") (pin "98") (pinfunction "PD15_98") (pintype "passive+no_connect"))
    )
    (net (code "113") (name "unconnected-(U1B-DSI_CKN-Pad107)") (class "Default")
      (node (ref "U1") (pin "107") (pinfunction "DSI_CKN_107") (pintype "passive+no_connect"))
    )
    (net (code "114") (name "unconnected-(U1B-DSI_CKP-Pad106)") (class "Default")
      (node (ref "U1") (pin "106") (pinfunction "DSI_CKP_106") (pintype "passive+no_connect"))
    )
    (net (code "115") (name "unconnected-(U1B-DSI_D0N-Pad104)") (class "Default")
      (node (ref "U1") (pin "104") (pinfunction "DSI_D0N_104") (pintype "passive+no_connect"))
    )
    (net (code "116") (name "unconnected-(U1B-DSI_D0P-Pad103)") (class "Default")
      (node (ref "U1") (pin "103") (pinfunction "DSI_D0P_103") (pintype "passive+no_connect"))
    )
    (net (code "117") (name "unconnected-(U1B-PE0-Pad170)") (class "Default")
      (node (ref "U1") (pin "170") (pinfunction "PE0_170") (pintype "passive+no_connect"))
    )
    (net (code "118") (name "unconnected-(U1B-PE1-Pad171)") (class "Default")
      (node (ref "U1") (pin "171") (pinfunction "PE1_171") (pintype "passive+no_connect"))
    )
    (net (code "119") (name "unconnected-(U1B-PE2-Pad1)") (class "Default")
      (node (ref "U1") (pin "1") (pinfunction "PE2_1") (pintype "passive+no_connect"))
    )
    (net (code "120") (name "unconnected-(U1B-PE3-Pad2)") (class "Default")
      (node (ref "U1") (pin "2") (pinfunction "PE3_2") (pintype "passive+no_connect"))
    )
    (net (code "121") (name "unconnected-(U1B-PE4-Pad3)") (class "Default")
      (node (ref "U1") (pin "3") (pinfunction "PE4_3") (pintype "passive+no_connect"))
    )
    (net (code "122") (name "unconnected-(U1B-PE5-Pad4)") (class "Default")
      (node (ref "U1") (pin "4") (pinfunction "PE5_4") (pintype "passive+no_connect"))
    )
    (net (code "123") (name "unconnected-(U1B-PE6-Pad5)") (class "Default")
      (node (ref "U1") (pin "5") (pinfunction "PE6_5") (pintype "passive+no_connect"))
    )
    (net (code "124") (name "unconnected-(U1B-PF3-Pad21)") (class "Default")
      (node (ref "U1") (pin "21") (pinfunction "PF3_21") (pintype "passive+no_connect"))
    )
    (net (code "125") (name "unconnected-(U1B-PF4-Pad22)") (class "Default")
      (node (ref "U1") (pin "22") (pinfunction "PF4_22") (pintype "passive+no_connect"))
    )
    (net (code "126") (name "unconnected-(U1B-PF5-Pad23)") (class "Default")
      (node (ref "U1") (pin "23") (pinfunction "PF5_23") (pintype "passive+no_connect"))
    )
    (net (code "127") (name "unconnected-(U1B-PF6-Pad26)") (class "Default")
      (node (ref "U1") (pin "26") (pinfunction "PF6_26") (pintype "passive+no_connect"))
    )
    (net (code "128") (name "unconnected-(U1B-PF11-Pad58)") (class "Default")
      (node (ref "U1") (pin "58") (pinfunction "PF11_58") (pintype "passive+no_connect"))
    )
    (net (code "129") (name "unconnected-(U1B-PF12-Pad59)") (class "Default")
      (node (ref "U1") (pin "59") (pinfunction "PF12_59") (pintype "passive+no_connect"))
    )
    (net (code "130") (name "unconnected-(U1B-PF13-Pad60)") (class "Default")
      (node (ref "U1") (pin "60") (pinfunction "PF13_60") (pintype "passive+no_connect"))
    )
    (net (code "131") (name "unconnected-(U1B-PG0-Pad63)") (class "Default")
      (node (ref "U1") (pin "63") (pinfunction "PG0_63") (pintype "passive+no_connect"))
    )
    (net (code "132") (name "unconnected-(U1B-PG1-Pad66)") (class "Default")
      (node (ref "U1") (pin "66") (pinfunction "PG1_66") (pintype "passive+no_connect"))
    )
    (net (code "133") (name "unconnected-(U1B-PG9-Pad153)") (class "Default")
      (node (ref "U1") (pin "153") (pinfunction "PG9_153") (pintype "passive+no_connect"))
    )
    (net (code "134") (name "unconnected-(U1B-PG13-Pad157)") (class "Default")
      (node (ref "U1") (pin "157") (pinfunction "PG13_157") (pintype "passive+no_connect"))
    )
    (net (code "135") (name "unconnected-(U1B-PG14-Pad158)") (class "Default")
      (node (ref "U1") (pin "158") (pinfunction "PG14_158") (pintype "passive+no_connect"))
    )
    (net (code "136") (name "unconnected-(U1B-PG15-Pad161)") (class "Default")
      (node (ref "U1") (pin "161") (pinfunction "PG15_161") (pintype "passive+no_connect"))
    )
    (net (code "137") (name "unconnected-(U1B-PH1-OSC_OUT-Pad32)") (class "Default")
      (node (ref "U1") (pin "32") (pinfunction "PH1-OSC_OUT_32") (pintype "passive+no_connect"))
    )
    (net (code "138") (name "unconnected-(U6-NC-Pad4)") (class "Default")
      (node (ref "U6") (pin "4") (pinfunction "NC_4") (pintype "passive+no_connect"))
    )
  )
)
